# plutosdr-revb-extclk.net
KiCad netlist of a schematic drawn in EAGLE
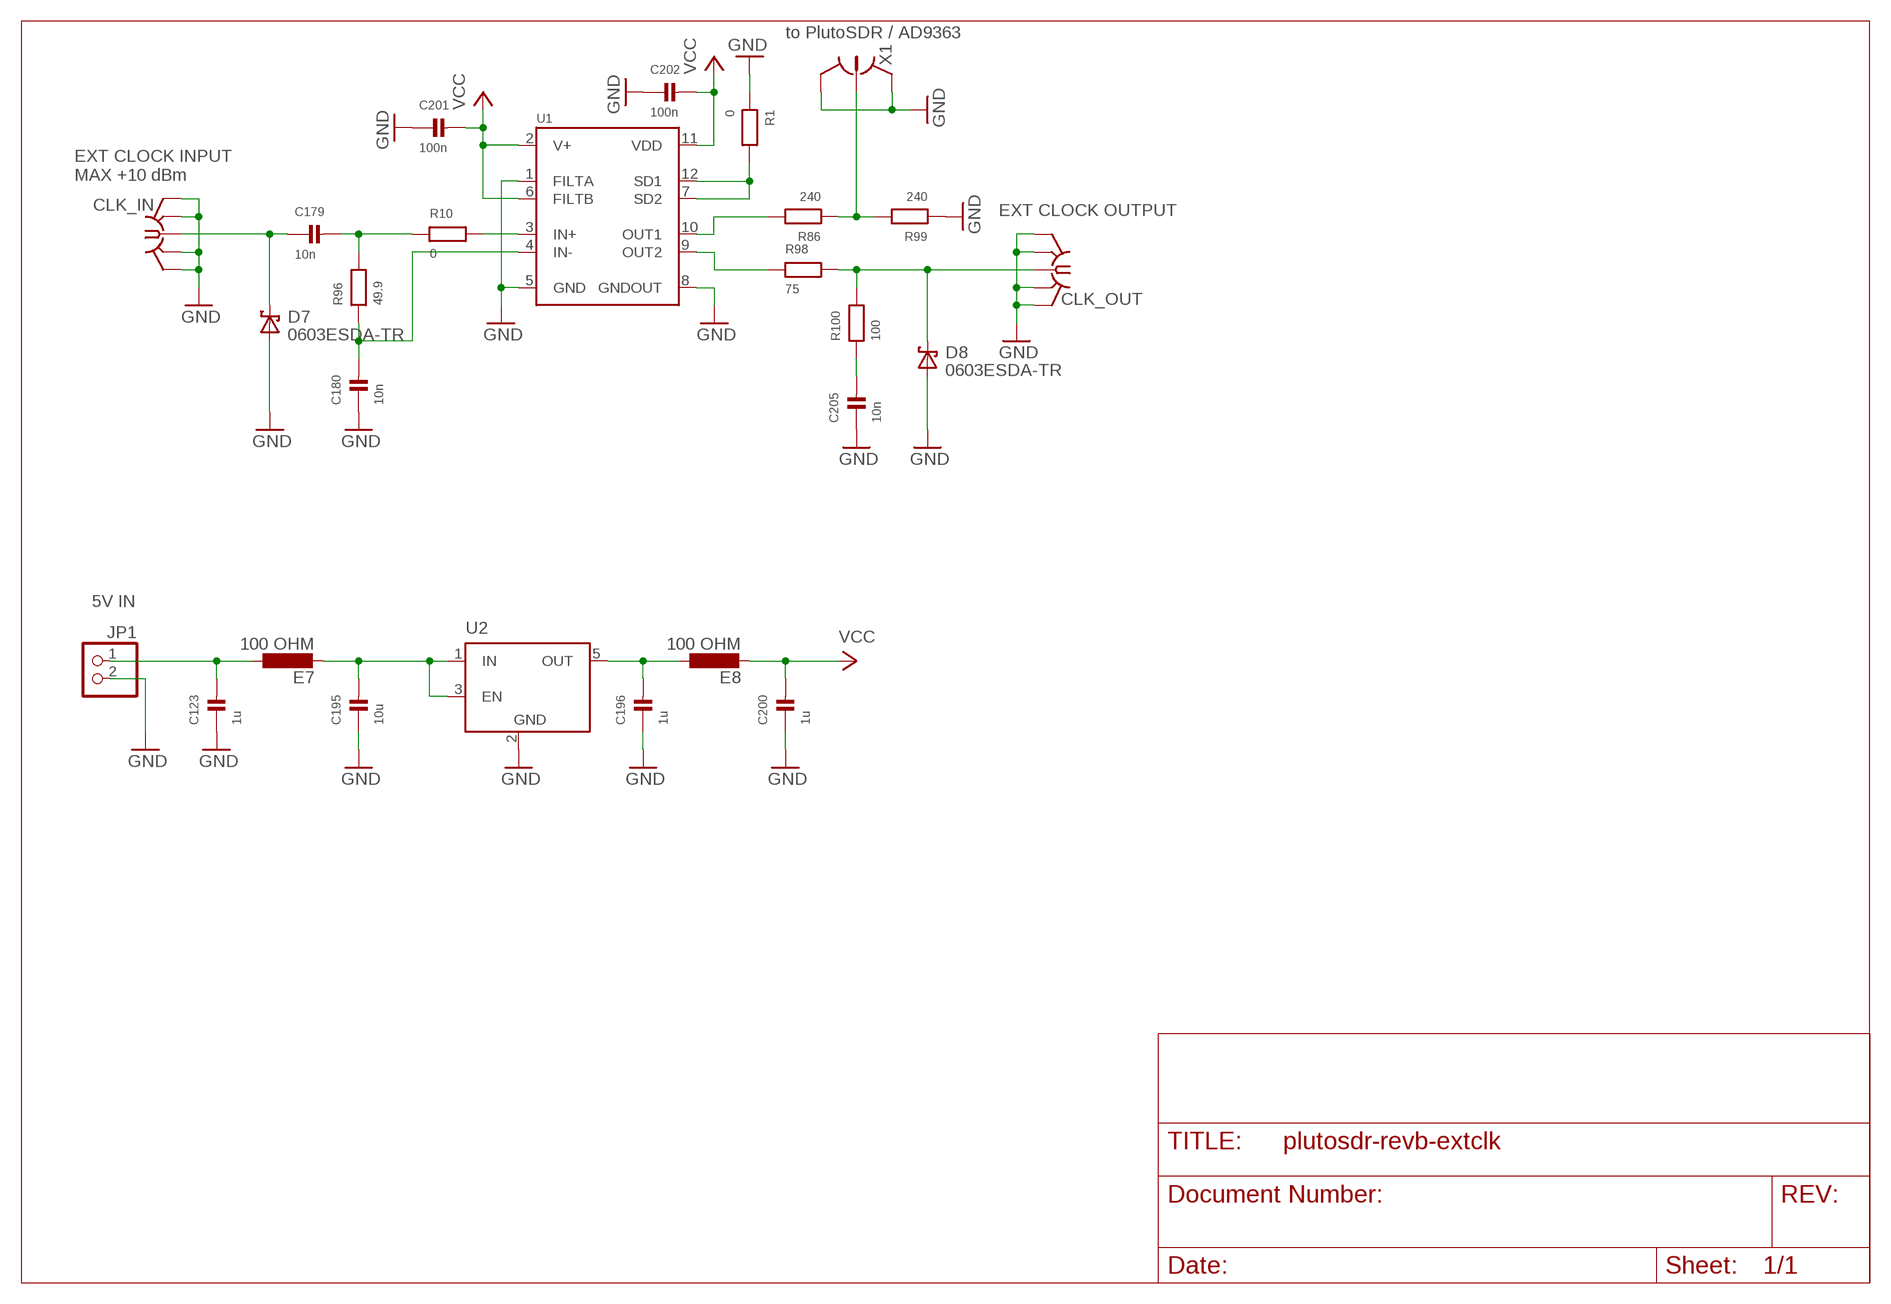
[diagram p0: schematic, sheet 1]

(export (version "E")
  (design (tool "Eeschema 10.0.6"))
  (components
    (comp (ref "C123")
      (value "1u")
      (footprint "eagle-import:_0603")
      (libsource (lib "eagle-import") (part "CAP_CERAMIC_0603"))
    )
    (comp (ref "C179")
      (value "10n")
      (footprint "eagle-import:_0603")
      (libsource (lib "eagle-import") (part "CAP_CERAMIC_0603"))
    )
    (comp (ref "C180")
      (value "10n")
      (footprint "eagle-import:_0603")
      (libsource (lib "eagle-import") (part "CAP_CERAMIC_0603"))
    )
    (comp (ref "C195")
      (value "10u")
      (footprint "eagle-import:_0805")
      (libsource (lib "eagle-import") (part "CAP_CERAMIC_0805"))
    )
    (comp (ref "C196")
      (value "1u")
      (footprint "eagle-import:_0603")
      (libsource (lib "eagle-import") (part "CAP_CERAMIC_0603"))
    )
    (comp (ref "C200")
      (value "1u")
      (footprint "eagle-import:_0603")
      (libsource (lib "eagle-import") (part "CAP_CERAMIC_0603"))
    )
    (comp (ref "C201")
      (value "100n")
      (footprint "eagle-import:_0603")
      (libsource (lib "eagle-import") (part "CAP_CERAMIC_0603"))
    )
    (comp (ref "C202")
      (value "100n")
      (footprint "eagle-import:_0603")
      (libsource (lib "eagle-import") (part "CAP_CERAMIC_0603"))
    )
    (comp (ref "C205")
      (value "10n")
      (footprint "eagle-import:_0603")
      (libsource (lib "eagle-import") (part "CAP_CERAMIC_0603"))
    )
    (comp (ref "CLK_IN")
      (value "SMA-F73251-2201")
      (footprint "eagle-import:SMA-F-S-TH-73251-2201")
      (libsource (lib "eagle-import") (part "SMA-F73251-2201"))
    )
    (comp (ref "CLK_OUT")
      (value "SMA-F73251-2201")
      (footprint "eagle-import:SMA-F-S-TH-73251-2201")
      (libsource (lib "eagle-import") (part "SMA-F73251-2201"))
    )
    (comp (ref "D7")
      (value "0603ESDA-TR")
      (footprint "eagle-import:0603")
      (libsource (lib "eagle-import") (part "0603ESDA-TR"))
    )
    (comp (ref "D8")
      (value "0603ESDA-TR")
      (footprint "eagle-import:0603")
      (libsource (lib "eagle-import") (part "0603ESDA-TR"))
    )
    (comp (ref "E7")
      (value "100 OHM")
      (footprint "eagle-import:0805")
      (libsource (lib "eagle-import") (part "INDUCTOR0805"))
    )
    (comp (ref "E8")
      (value "100 OHM")
      (footprint "eagle-import:0805")
      (libsource (lib "eagle-import") (part "INDUCTOR0805"))
    )
    (comp (ref "JP1")
      (value "PINHD-1X2/90")
      (footprint "eagle-import:1X02_90")
      (libsource (lib "eagle-import") (part "PINHD-1X2/90"))
    )
    (comp (ref "R1")
      (value "0")
      (footprint "eagle-import:_0603")
      (libsource (lib "eagle-import") (part "RESISTOR_0603"))
    )
    (comp (ref "R10")
      (value "0")
      (footprint "eagle-import:_0603")
      (libsource (lib "eagle-import") (part "RESISTOR_0603"))
    )
    (comp (ref "R86")
      (value "240")
      (footprint "eagle-import:_0603")
      (libsource (lib "eagle-import") (part "RESISTOR_0603"))
    )
    (comp (ref "R96")
      (value "49.9")
      (footprint "eagle-import:_0603")
      (libsource (lib "eagle-import") (part "RESISTOR_0603"))
    )
    (comp (ref "R98")
      (value "75")
      (footprint "eagle-import:_0603")
      (libsource (lib "eagle-import") (part "RESISTOR_0603"))
    )
    (comp (ref "R99")
      (value "240")
      (footprint "eagle-import:_0603")
      (libsource (lib "eagle-import") (part "RESISTOR_0603"))
    )
    (comp (ref "R100")
      (value "100")
      (footprint "eagle-import:_0603")
      (libsource (lib "eagle-import") (part "RESISTOR_0603"))
    )
    (comp (ref "U1")
      (value "LTC6957-3/4-HMS")
      (footprint "eagle-import:MSOP12")
      (libsource (lib "eagle-import") (part "LTC6957-3/4-HMS"))
    )
    (comp (ref "U2")
      (value "LDO_FIXED_EN-ADM7160AUJZ")
      (footprint "eagle-import:SOT23L")
      (libsource (lib "eagle-import") (part "LDO_FIXED_EN-ADM7160AUJZ"))
    )
    (comp (ref "X1")
      (value "HRS_UFL")
      (footprint "eagle-import:HRS_UFL")
      (libsource (lib "eagle-import") (part "HRS_UFL"))
    )
  )
  (nets
    (net (code "1") (name "GND") (class "Default")
      (node (ref "C123") (pin "1") (pinfunction "1_1") (pintype "passive"))
      (node (ref "C180") (pin "1") (pinfunction "1_1") (pintype "passive"))
      (node (ref "C195") (pin "1") (pinfunction "1_1") (pintype "passive"))
      (node (ref "C196") (pin "1") (pinfunction "1_1") (pintype "passive"))
      (node (ref "C200") (pin "1") (pinfunction "1_1") (pintype "passive"))
      (node (ref "C201") (pin "1") (pinfunction "1_1") (pintype "passive"))
      (node (ref "C202") (pin "1") (pinfunction "1_1") (pintype "passive"))
      (node (ref "C205") (pin "1") (pinfunction "1_1") (pintype "passive"))
      (node (ref "CLK_IN") (pin "G1") (pinfunction "GND_G1") (pintype "power_in"))
      (node (ref "CLK_IN") (pin "G2") (pinfunction "GND_G2") (pintype "power_in"))
      (node (ref "CLK_IN") (pin "G3") (pinfunction "GND_G3") (pintype "power_in"))
      (node (ref "CLK_IN") (pin "G4") (pinfunction "GND_G4") (pintype "power_in"))
      (node (ref "CLK_OUT") (pin "G1") (pinfunction "GND_G1") (pintype "power_in"))
      (node (ref "CLK_OUT") (pin "G2") (pinfunction "GND_G2") (pintype "power_in"))
      (node (ref "CLK_OUT") (pin "G3") (pinfunction "GND_G3") (pintype "power_in"))
      (node (ref "CLK_OUT") (pin "G4") (pinfunction "GND_G4") (pintype "power_in"))
      (node (ref "D7") (pin "1") (pinfunction "A_1") (pintype "passive"))
      (node (ref "D8") (pin "1") (pinfunction "A_1") (pintype "passive"))
      (node (ref "JP1") (pin "2") (pinfunction "2_2") (pintype "passive"))
      (node (ref "R1") (pin "1") (pinfunction "1_1") (pintype "passive"))
      (node (ref "R99") (pin "1") (pinfunction "1_1") (pintype "passive"))
      (node (ref "U1") (pin "1") (pinfunction "FILTA_1") (pintype "input"))
      (node (ref "U1") (pin "5") (pinfunction "GND_5") (pintype "passive"))
      (node (ref "U1") (pin "8") (pinfunction "GNDOUT_8") (pintype "passive"))
      (node (ref "U2") (pin "2") (pinfunction "GND_2") (pintype "power_in"))
      (node (ref "X1") (pin "GND@1") (pinfunction "GND_GND@1") (pintype "power_in"))
      (node (ref "X1") (pin "GND@2") (pinfunction "GND_GND@2") (pintype "power_in"))
    )
    (net (code "2") (name "Net-(C123-Pad2)") (class "Default")
      (node (ref "C123") (pin "2") (pinfunction "2_2") (pintype "passive"))
      (node (ref "E7") (pin "1") (pinfunction "1_1") (pintype "passive"))
      (node (ref "JP1") (pin "1") (pinfunction "1_1") (pintype "passive"))
    )
    (net (code "3") (name "Net-(C179-Pad2)") (class "Default")
      (node (ref "C179") (pin "2") (pinfunction "2_2") (pintype "passive"))
      (node (ref "R10") (pin "1") (pinfunction "1_1") (pintype "passive"))
      (node (ref "R96") (pin "2") (pinfunction "2_2") (pintype "passive"))
    )
    (net (code "4") (name "Net-(C205-Pad2)") (class "Default")
      (node (ref "C205") (pin "2") (pinfunction "2_2") (pintype "passive"))
      (node (ref "R100") (pin "1") (pinfunction "1_1") (pintype "passive"))
    )
    (net (code "5") (name "Net-(CLK_IN-1)") (class "Default")
      (node (ref "C179") (pin "1") (pinfunction "1_1") (pintype "passive"))
      (node (ref "CLK_IN") (pin "C") (pinfunction "1_C") (pintype "passive"))
      (node (ref "D7") (pin "2") (pinfunction "K_2") (pintype "passive"))
    )
    (net (code "6") (name "Net-(CLK_OUT-1)") (class "Default")
      (node (ref "CLK_OUT") (pin "C") (pinfunction "1_C") (pintype "passive"))
      (node (ref "D8") (pin "2") (pinfunction "K_2") (pintype "passive"))
      (node (ref "R100") (pin "2") (pinfunction "2_2") (pintype "passive"))
      (node (ref "R98") (pin "2") (pinfunction "2_2") (pintype "passive"))
    )
    (net (code "7") (name "Net-(U1-IN+)") (class "Default")
      (node (ref "R10") (pin "2") (pinfunction "2_2") (pintype "passive"))
      (node (ref "U1") (pin "3") (pinfunction "IN+_3") (pintype "input"))
    )
    (net (code "8") (name "Net-(U1-IN-)") (class "Default")
      (node (ref "C180") (pin "2") (pinfunction "2_2") (pintype "passive"))
      (node (ref "R96") (pin "1") (pinfunction "1_1") (pintype "passive"))
      (node (ref "U1") (pin "4") (pinfunction "IN-_4") (pintype "input"))
    )
    (net (code "9") (name "Net-(U1-OUT1)") (class "Default")
      (node (ref "R86") (pin "2") (pinfunction "2_2") (pintype "passive"))
      (node (ref "U1") (pin "10") (pinfunction "OUT1_10") (pintype "output"))
    )
    (net (code "10") (name "Net-(U1-OUT2)") (class "Default")
      (node (ref "R98") (pin "1") (pinfunction "1_1") (pintype "passive"))
      (node (ref "U1") (pin "9") (pinfunction "OUT2_9") (pintype "output"))
    )
    (net (code "11") (name "Net-(U1-SD1)") (class "Default")
      (node (ref "R1") (pin "2") (pinfunction "2_2") (pintype "passive"))
      (node (ref "U1") (pin "12") (pinfunction "SD1_12") (pintype "input"))
      (node (ref "U1") (pin "7") (pinfunction "SD2_7") (pintype "input"))
    )
    (net (code "12") (name "Net-(U2-EN)") (class "Default")
      (node (ref "C195") (pin "2") (pinfunction "2_2") (pintype "passive"))
      (node (ref "E7") (pin "2") (pinfunction "2_2") (pintype "passive"))
      (node (ref "U2") (pin "1") (pinfunction "IN_1") (pintype "input"))
      (node (ref "U2") (pin "3") (pinfunction "EN_3") (pintype "input"))
    )
    (net (code "13") (name "Net-(U2-OUT)") (class "Default")
      (node (ref "C196") (pin "2") (pinfunction "2_2") (pintype "passive"))
      (node (ref "E8") (pin "1") (pinfunction "1_1") (pintype "passive"))
      (node (ref "U2") (pin "5") (pinfunction "OUT_5") (pintype "passive"))
    )
    (net (code "14") (name "Net-(X1-1)") (class "Default")
      (node (ref "R86") (pin "1") (pinfunction "1_1") (pintype "passive"))
      (node (ref "R99") (pin "2") (pinfunction "2_2") (pintype "passive"))
      (node (ref "X1") (pin "SIG") (pinfunction "1_SIG") (pintype "passive"))
    )
    (net (code "15") (name "VCC") (class "Default")
      (node (ref "C200") (pin "2") (pinfunction "2_2") (pintype "passive"))
      (node (ref "C201") (pin "2") (pinfunction "2_2") (pintype "passive"))
      (node (ref "C202") (pin "2") (pinfunction "2_2") (pintype "passive"))
      (node (ref "E8") (pin "2") (pinfunction "2_2") (pintype "passive"))
      (node (ref "U1") (pin "11") (pinfunction "VDD_11") (pintype "passive"))
      (node (ref "U1") (pin "2") (pinfunction "V+_2") (pintype "passive"))
      (node (ref "U1") (pin "6") (pinfunction "FILTB_6") (pintype "input"))
    )
  )
)
